# LPCB220_-_BRAKE_MLP_CHANNEL.net
KiCad netlist of a schematic drawn in Altium Designer
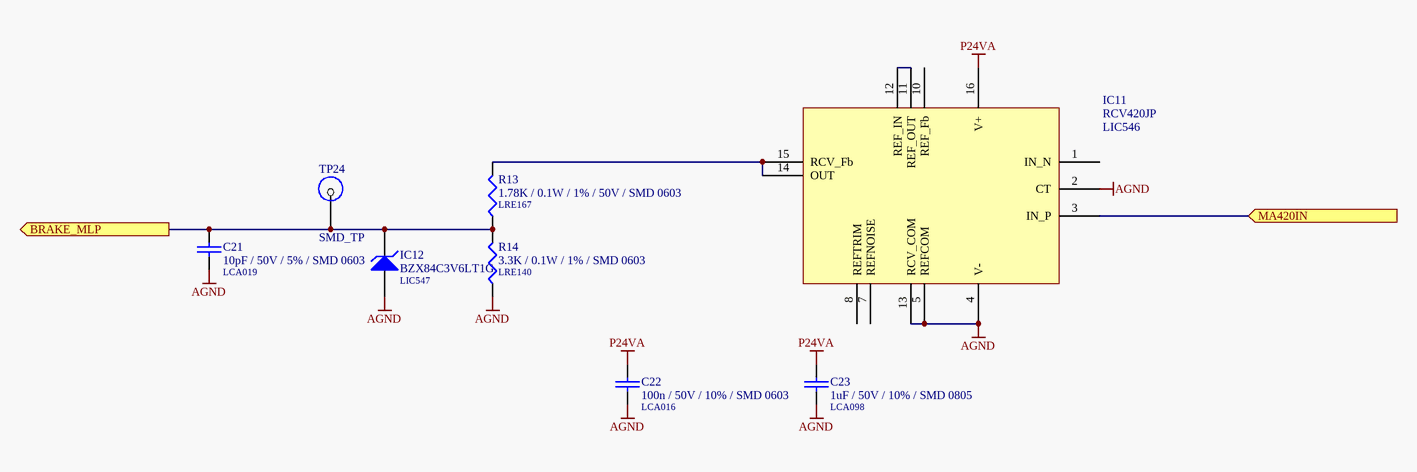
[diagram p0: LPCB220 - BRAKE MLP CHANNEL.SchDoc]

(export (version "E")
  (design (tool "Eeschema 10.0.6"))
  (components
    (comp (ref "C21")
      (value "10pF / 50V / 5% / SMD 0603")
      (footprint "LFP011__CC1608-0603-IPC7351_B")
      (description "Capacitor, Ceramic Chip, 10pF, 50V, 5%, SMD 0603 [LCA019]")
      (fields (field (name "LDL_NUMBER") "LCA019"))
      (libsource (lib "LDL_Capacitors") (part "10pF / 50V / 5% / SMD 0603"))
    )
    (comp (ref "C22")
      (value "100n / 50V / 10% / SMD 0603")
      (footprint "LFP011__CC1608-0603-IPC7351_B")
      (description "Capacitor, Ceramic Chip, 100nF (0.1uF), 50V, 5%, SMD 0603 [LCA016]")
      (fields (field (name "LDL_NUMBER") "LCA016"))
      (libsource (lib "LDL_Capacitors") (part "100n / 50V / 10% / SMD 0603"))
    )
    (comp (ref "C23")
      (value "1uF / 50V / 10% / SMD 0805")
      (footprint "LFP010__CC2012-0805-IPC7351_B")
      (description "Capacitor, Ceramic Chip, 1uF, 50V, SMD 0805 [LCA098]")
      (fields (field (name "LDL_NUMBER") "LCA098"))
      (libsource (lib "LDL_Capacitors") (part "1uF / 50V / 10% / SMD 0805"))
    )
    (comp (ref "IC11")
      (value "RCV420JP")
      (footprint "DIP-P16/X1.5")
      (description "IC, 4-20mA Interface, DIP16 [LIC546]")
      (fields (field (name "LDL_NUMBER") "LIC546"))
      (libsource (lib "LDL_Semiconductors") (part "RCV420JP"))
    )
    (comp (ref "IC12")
      (value "BZX84C3V6LT1G")
      (footprint "LFP021__SOT23")
      (description "Diode, Zener, 3.6V, 0.225W, SMD [LIC083]")
      (fields (field (name "LDL_NUMBER") "LIC547"))
      (libsource (lib "LDL_Semiconductors") (part "BZX84C3V6LT1G"))
    )
    (comp (ref "R13")
      (value "1.78K / 0.1W / 1% / 50V / SMD 0603")
      (footprint "LFP020__CR1608-0603-IPC7351_B")
      (description "Resistor, Ceramic Chip, 1.78K, 0.1W, 1%, SMD 0603 [LRE167]")
      (fields (field (name "LDL_NUMBER") "LRE167"))
      (libsource (lib "LDL_Resistors") (part "1.78K / 0.1W / 1% / 50V / SMD 0603"))
    )
    (comp (ref "R14")
      (value "3.3K / 0.1W / 1% / SMD 0603")
      (footprint "LFP020__CR1608-0603-IPC7351_B")
      (description "Resistor, Ceramic Chip, 3.3K0, 0.1W, 1%, SMD 0603 [LRE140]")
      (fields (field (name "LDL_NUMBER") "LRE140"))
      (libsource (lib "LDL_Resistors") (part "3.3K / 0.1W / 1% / SMD 0603"))
    )
    (comp (ref "TP24")
      (value "SMD_TP")
      (footprint "SMD-TP")
      (description "SMD Test Point")
      (libsource (lib "LDL_Connectors") (part "SMD_TP"))
    )
  )
  (nets
    (net (code "1") (name "/BRAKE_MLP") (class "Default")
      (node (ref "C21") (pin "1") (pintype "passive"))
      (node (ref "IC12") (pin "3") (pinfunction "K_3") (pintype "passive"))
      (node (ref "R13") (pin "1") (pintype "passive"))
      (node (ref "R14") (pin "2") (pintype "passive"))
      (node (ref "TP24") (pin "1") (pintype "passive"))
    )
    (net (code "2") (name "/MA420IN") (class "Default")
      (node (ref "IC11") (pin "3") (pinfunction "IN_P_3") (pintype "passive"))
    )
    (net (code "3") (name "AGND") (class "Default")
      (node (ref "C21") (pin "2") (pintype "passive"))
      (node (ref "C22") (pin "2") (pintype "passive"))
      (node (ref "C23") (pin "2") (pintype "passive"))
      (node (ref "IC11") (pin "13") (pinfunction "RCV_COM_13") (pintype "passive"))
      (node (ref "IC11") (pin "2") (pinfunction "CT_2") (pintype "passive"))
      (node (ref "IC11") (pin "4") (pinfunction "V-_4") (pintype "power_in"))
      (node (ref "IC11") (pin "5") (pinfunction "REFCOM_5") (pintype "passive"))
      (node (ref "IC12") (pin "1") (pinfunction "A_1") (pintype "passive"))
      (node (ref "R14") (pin "1") (pintype "passive"))
    )
    (net (code "4") (name "Net-(IC11-OUT)") (class "Default")
      (node (ref "IC11") (pin "14") (pinfunction "OUT_14") (pintype "passive"))
      (node (ref "IC11") (pin "15") (pinfunction "RCV_Fb_15") (pintype "passive"))
      (node (ref "R13") (pin "2") (pintype "passive"))
    )
    (net (code "5") (name "Net-(IC11-REF_IN)") (class "Default")
      (node (ref "IC11") (pin "11") (pinfunction "REF_OUT_11") (pintype "passive"))
      (node (ref "IC11") (pin "12") (pinfunction "REF_IN_12") (pintype "passive"))
    )
    (net (code "6") (name "P24VA") (class "Default")
      (node (ref "C22") (pin "1") (pintype "passive"))
      (node (ref "C23") (pin "1") (pintype "passive"))
      (node (ref "IC11") (pin "16") (pinfunction "V+_16") (pintype "power_in"))
    )
    (net (code "7") (name "unconnected-(IC11-IN_N-Pad1)") (class "Default")
      (node (ref "IC11") (pin "1") (pinfunction "IN_N_1") (pintype "passive"))
    )
    (net (code "8") (name "unconnected-(IC11-REFNOISE-Pad7)") (class "Default")
      (node (ref "IC11") (pin "7") (pinfunction "REFNOISE_7") (pintype "passive"))
    )
    (net (code "9") (name "unconnected-(IC11-REFTRIM-Pad8)") (class "Default")
      (node (ref "IC11") (pin "8") (pinfunction "REFTRIM_8") (pintype "passive"))
    )
    (net (code "10") (name "unconnected-(IC11-REF_Fb-Pad10)") (class "Default")
      (node (ref "IC11") (pin "10") (pinfunction "REF_Fb_10") (pintype "passive"))
    )
  )
)
